# V4-AddOnESP8266-V02-004.net
KiCad netlist of a schematic drawn in EAGLE
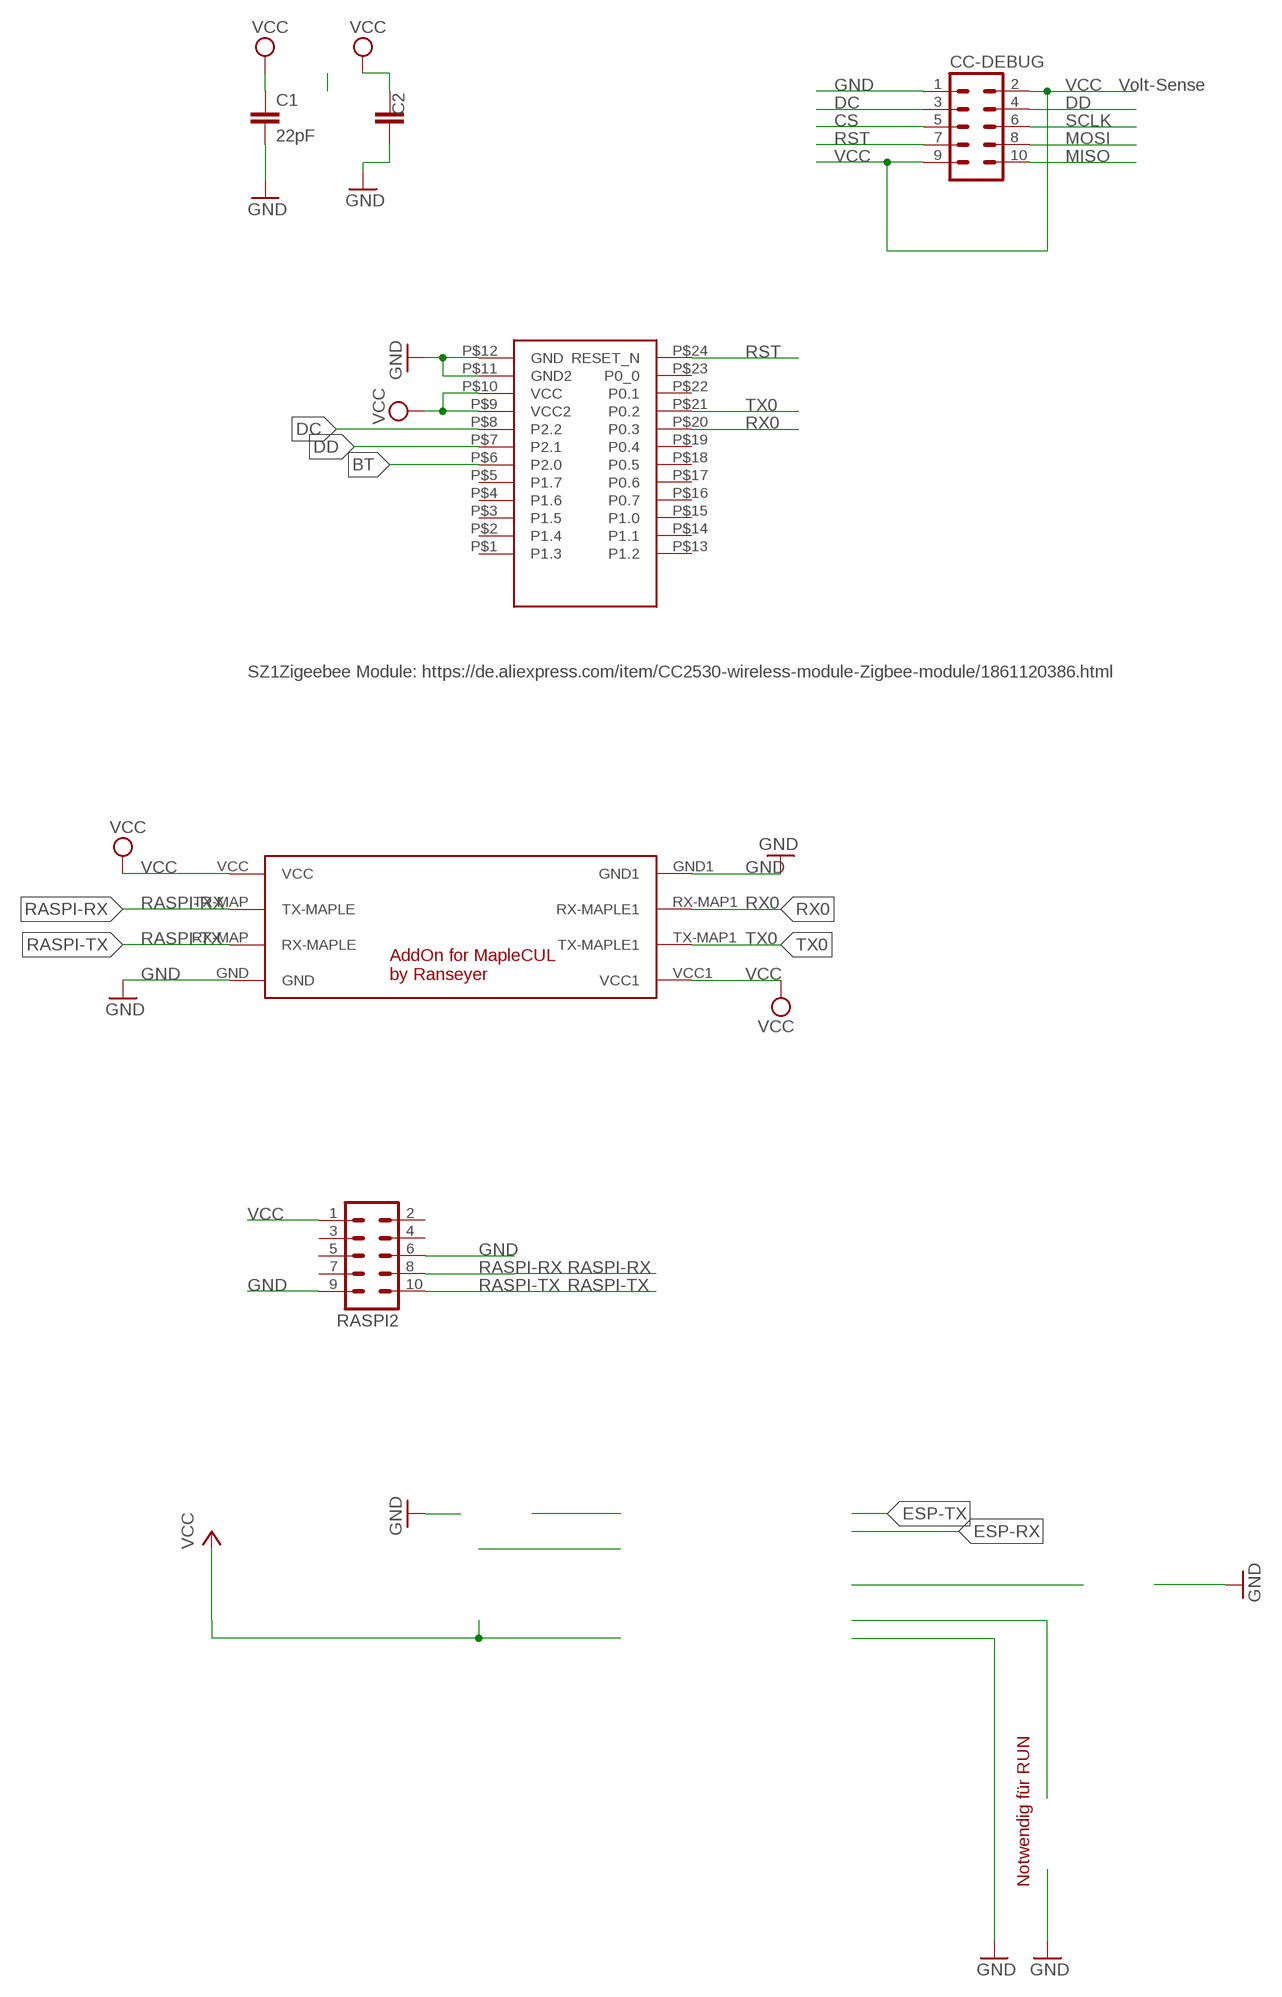
[diagram p0: schematic, sheet 1]

(export (version "E")
  (design (tool "Eeschema 10.0.6"))
  (components
    (comp (ref "C1")
      (value "22pF")
      (footprint "eagle-import:C0805")
      (libsource (lib "eagle-import") (part "C-EUC0805"))
    )
    (comp (ref "C2")
      (value "C-EUC1812")
      (footprint "eagle-import:C1812")
      (libsource (lib "eagle-import") (part "C-EUC1812"))
    )
    (comp (ref "CC-DEBUG")
      (value "CONN_05X2SHD_LOCK")
      (footprint "eagle-import:2X5-SHROUDED_LOCK")
      (libsource (lib "eagle-import") (part "CONN_05X2SHD_LOCK"))
    )
    (comp (ref "RASPI2")
      (value "MA05-2")
      (footprint "eagle-import:MA05-2")
      (libsource (lib "eagle-import") (part "MA05-2"))
    )
    (comp (ref "U$1")
      (value "MAPLE-CUL-ADDON-V01")
      (footprint "eagle-import:MAPLE-CUL-V01")
      (libsource (lib "eagle-import") (part "MAPLE-CUL-ADDON-V01"))
    )
    (comp (ref "U$2")
      (value "CC2530")
      (footprint "eagle-import:SZ1ZIGBEE-SMD")
      (libsource (lib "eagle-import") (part "CC2530"))
    )
  )
  (nets
    (net (code "1") (name "/CS") (class "Default")
      (node (ref "CC-DEBUG") (pin "5") (pinfunction "5_5") (pintype "passive"))
    )
    (net (code "2") (name "/MISO") (class "Default")
      (node (ref "CC-DEBUG") (pin "10") (pinfunction "10_10") (pintype "passive"))
    )
    (net (code "3") (name "/MOSI") (class "Default")
      (node (ref "CC-DEBUG") (pin "8") (pinfunction "8_8") (pintype "passive"))
    )
    (net (code "4") (name "/RST") (class "Default")
      (node (ref "CC-DEBUG") (pin "7") (pinfunction "7_7") (pintype "passive"))
      (node (ref "U$2") (pin "P$24") (pinfunction "RESET_N_P$24") (pintype "bidirectional"))
    )
    (net (code "5") (name "/SCLK") (class "Default")
      (node (ref "CC-DEBUG") (pin "6") (pinfunction "6_6") (pintype "passive"))
    )
    (net (code "6") (name "BT") (class "Default")
      (node (ref "U$2") (pin "P$6") (pinfunction "P2.0_P$6") (pintype "bidirectional"))
    )
    (net (code "7") (name "DC") (class "Default")
      (node (ref "CC-DEBUG") (pin "3") (pinfunction "3_3") (pintype "passive"))
      (node (ref "U$2") (pin "P$8") (pinfunction "P2.2_P$8") (pintype "bidirectional"))
    )
    (net (code "8") (name "DD") (class "Default")
      (node (ref "CC-DEBUG") (pin "4") (pinfunction "4_4") (pintype "passive"))
      (node (ref "U$2") (pin "P$7") (pinfunction "P2.1_P$7") (pintype "bidirectional"))
    )
    (net (code "11") (name "GND") (class "Default")
      (node (ref "C1") (pin "2") (pinfunction "2_2") (pintype "passive"))
      (node (ref "C2") (pin "1") (pinfunction "1_1") (pintype "passive"))
      (node (ref "CC-DEBUG") (pin "1") (pinfunction "1_1") (pintype "passive"))
      (node (ref "RASPI2") (pin "6") (pinfunction "6_6") (pintype "passive"))
      (node (ref "RASPI2") (pin "9") (pinfunction "9_9") (pintype "passive"))
      (node (ref "U$1") (pin "GND") (pinfunction "GND_GND") (pintype "bidirectional"))
      (node (ref "U$1") (pin "GND1") (pinfunction "GND1_GND1") (pintype "bidirectional"))
      (node (ref "U$2") (pin "P$11") (pinfunction "GND2_P$11") (pintype "bidirectional"))
      (node (ref "U$2") (pin "P$12") (pinfunction "GND_P$12") (pintype "bidirectional"))
    )
    (net (code "12") (name "RASPI-RX") (class "Default")
      (node (ref "RASPI2") (pin "8") (pinfunction "8_8") (pintype "passive"))
      (node (ref "U$1") (pin "TX-MAP") (pinfunction "TX-MAPLE_TX-MAP") (pintype "bidirectional"))
    )
    (net (code "13") (name "RASPI-TX") (class "Default")
      (node (ref "RASPI2") (pin "10") (pinfunction "10_10") (pintype "passive"))
      (node (ref "U$1") (pin "RX-MAP") (pinfunction "RX-MAPLE_RX-MAP") (pintype "bidirectional"))
    )
    (net (code "14") (name "RX0") (class "Default")
      (node (ref "U$1") (pin "RX-MAP1") (pinfunction "RX-MAPLE1_RX-MAP1") (pintype "bidirectional"))
      (node (ref "U$2") (pin "P$20") (pinfunction "P0.3_P$20") (pintype "bidirectional"))
    )
    (net (code "15") (name "TX0") (class "Default")
      (node (ref "U$1") (pin "TX-MAP1") (pinfunction "TX-MAPLE1_TX-MAP1") (pintype "bidirectional"))
      (node (ref "U$2") (pin "P$21") (pinfunction "P0.2_P$21") (pintype "bidirectional"))
    )
    (net (code "16") (name "VCC") (class "Default")
      (node (ref "C1") (pin "1") (pinfunction "1_1") (pintype "passive"))
      (node (ref "C2") (pin "2") (pinfunction "2_2") (pintype "passive"))
      (node (ref "CC-DEBUG") (pin "2") (pinfunction "2_2") (pintype "passive"))
      (node (ref "CC-DEBUG") (pin "9") (pinfunction "9_9") (pintype "passive"))
      (node (ref "RASPI2") (pin "1") (pinfunction "1_1") (pintype "passive"))
      (node (ref "U$1") (pin "VCC") (pinfunction "VCC_VCC") (pintype "bidirectional"))
      (node (ref "U$1") (pin "VCC1") (pinfunction "VCC1_VCC1") (pintype "bidirectional"))
      (node (ref "U$2") (pin "P$10") (pinfunction "VCC_P$10") (pintype "bidirectional"))
      (node (ref "U$2") (pin "P$9") (pinfunction "VCC2_P$9") (pintype "bidirectional"))
    )
    (net (code "17") (name "unconnected-(RASPI2-Pad2)") (class "Default")
      (node (ref "RASPI2") (pin "2") (pinfunction "2_2") (pintype "passive"))
    )
    (net (code "18") (name "unconnected-(RASPI2-Pad3)") (class "Default")
      (node (ref "RASPI2") (pin "3") (pinfunction "3_3") (pintype "passive"))
    )
    (net (code "19") (name "unconnected-(RASPI2-Pad4)") (class "Default")
      (node (ref "RASPI2") (pin "4") (pinfunction "4_4") (pintype "passive"))
    )
    (net (code "20") (name "unconnected-(RASPI2-Pad5)") (class "Default")
      (node (ref "RASPI2") (pin "5") (pinfunction "5_5") (pintype "passive"))
    )
    (net (code "21") (name "unconnected-(RASPI2-Pad7)") (class "Default")
      (node (ref "RASPI2") (pin "7") (pinfunction "7_7") (pintype "passive"))
    )
    (net (code "22") (name "unconnected-(U$2-P0.1-PadP$22)") (class "Default")
      (node (ref "U$2") (pin "P$22") (pinfunction "P0.1_P$22") (pintype "bidirectional"))
    )
    (net (code "23") (name "unconnected-(U$2-P0.4-PadP$19)") (class "Default")
      (node (ref "U$2") (pin "P$19") (pinfunction "P0.4_P$19") (pintype "bidirectional"))
    )
    (net (code "24") (name "unconnected-(U$2-P0.5-PadP$18)") (class "Default")
      (node (ref "U$2") (pin "P$18") (pinfunction "P0.5_P$18") (pintype "bidirectional"))
    )
    (net (code "25") (name "unconnected-(U$2-P0.6-PadP$17)") (class "Default")
      (node (ref "U$2") (pin "P$17") (pinfunction "P0.6_P$17") (pintype "bidirectional"))
    )
    (net (code "26") (name "unconnected-(U$2-P0.7-PadP$16)") (class "Default")
      (node (ref "U$2") (pin "P$16") (pinfunction "P0.7_P$16") (pintype "bidirectional"))
    )
    (net (code "27") (name "unconnected-(U$2-P0_0-PadP$23)") (class "Default")
      (node (ref "U$2") (pin "P$23") (pinfunction "P0_0_P$23") (pintype "bidirectional"))
    )
    (net (code "28") (name "unconnected-(U$2-P1.0-PadP$15)") (class "Default")
      (node (ref "U$2") (pin "P$15") (pinfunction "P1.0_P$15") (pintype "bidirectional"))
    )
    (net (code "29") (name "unconnected-(U$2-P1.1-PadP$14)") (class "Default")
      (node (ref "U$2") (pin "P$14") (pinfunction "P1.1_P$14") (pintype "bidirectional"))
    )
    (net (code "30") (name "unconnected-(U$2-P1.2-PadP$13)") (class "Default")
      (node (ref "U$2") (pin "P$13") (pinfunction "P1.2_P$13") (pintype "bidirectional"))
    )
    (net (code "31") (name "unconnected-(U$2-P1.3-PadP$1)") (class "Default")
      (node (ref "U$2") (pin "P$1") (pinfunction "P1.3_P$1") (pintype "bidirectional"))
    )
    (net (code "32") (name "unconnected-(U$2-P1.4-PadP$2)") (class "Default")
      (node (ref "U$2") (pin "P$2") (pinfunction "P1.4_P$2") (pintype "bidirectional"))
    )
    (net (code "33") (name "unconnected-(U$2-P1.5-PadP$3)") (class "Default")
      (node (ref "U$2") (pin "P$3") (pinfunction "P1.5_P$3") (pintype "bidirectional"))
    )
    (net (code "34") (name "unconnected-(U$2-P1.6-PadP$4)") (class "Default")
      (node (ref "U$2") (pin "P$4") (pinfunction "P1.6_P$4") (pintype "bidirectional"))
    )
    (net (code "35") (name "unconnected-(U$2-P1.7-PadP$5)") (class "Default")
      (node (ref "U$2") (pin "P$5") (pinfunction "P1.7_P$5") (pintype "bidirectional"))
    )
  )
)
